# Alimentacion.net
KiCad netlist of a schematic drawn in Altium Designer
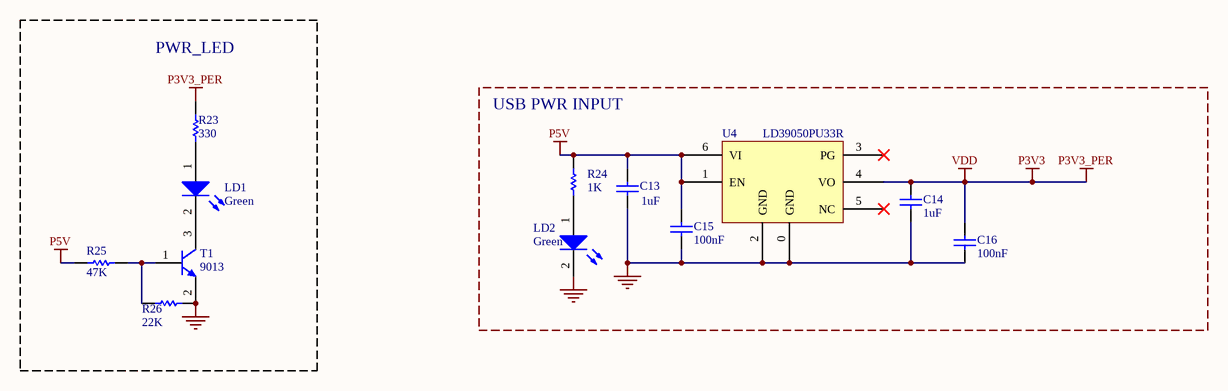
[diagram p0: Alimentacion.SchDoc]

(export (version "E")
  (design (tool "Eeschema 10.0.6"))
  (components
    (comp (ref "C13")
      (value "1uF")
      (footprint "0603C")
      (description "0603  X5R 1µF")
      (fields (field (name "TOLERANCE") "10%"))
      (libsource (lib "MB963_1") (part "CAP SMD 0603  X5R 1µF 25V 10%"))
    )
    (comp (ref "C14")
      (value "1uF")
      (footprint "0603C")
      (description "0603  X5R 1µF")
      (fields (field (name "TOLERANCE") "10%"))
      (libsource (lib "MB963_1") (part "CAP SMD 0603  X5R 1µF 25V 10%"))
    )
    (comp (ref "C15")
      (value "100nF")
      (footprint "0603C")
      (description "Capacitor 0402 / 0603 / 0805")
      (libsource (lib "MCD_TOOLS") (part "Capacitor_ST"))
    )
    (comp (ref "C16")
      (value "100nF")
      (footprint "0603C")
      (description "Capacitor 0402 / 0603 / 0805")
      (libsource (lib "MCD_TOOLS") (part "Capacitor_ST"))
    )
    (comp (ref "LD1")
      (value "Green")
      (footprint "0603D-G")
      (description "Typical RED, GREEN, YELLOW, AMBER GaAs LED")
      (fields (field (name "PUBLISHER") "Altium Limited"))
      (libsource (lib "") (part "LED2_1"))
    )
    (comp (ref "LD2")
      (value "Green")
      (footprint "0603D-G")
      (description "Typical RED, GREEN, YELLOW, AMBER GaAs LED")
      (fields (field (name "PUBLISHER") "Altium Limited"))
      (libsource (lib "Miscellaneous Devices") (part "LED2"))
    )
    (comp (ref "R23")
      (value "330")
      (footprint "0603R")
      (description "Resistor")
      (fields (field (name "PUBLISHER") "Altium Limited"))
      (libsource (lib "Miscellaneous Devices") (part "res1"))
    )
    (comp (ref "R24")
      (value "1K")
      (footprint "0603R")
      (description "Resistor 0402 / 0603 / 0805")
      (libsource (lib "MCD_TOOLS") (part "Resistor_ST"))
    )
    (comp (ref "R25")
      (value "47K")
      (footprint "0603R")
      (description "Resistor")
      (fields (field (name "PUBLISHER") "Altium Limited"))
      (libsource (lib "Miscellaneous Devices") (part "res1"))
    )
    (comp (ref "R26")
      (value "22K")
      (footprint "0603R")
      (description "Resistor")
      (fields (field (name "PUBLISHER") "Altium Limited"))
      (libsource (lib "Miscellaneous Devices") (part "res1"))
    )
    (comp (ref "T1")
      (value "9013")
      (footprint "SOT-23")
      (description "NPN Bipolar Transistor")
      (fields (field (name "PUBLISHER") "Altium Limited"))
      (libsource (lib "MB1167") (part "NPN"))
    )
    (comp (ref "U4")
      (value "LD39050PU33R")
      (footprint "DFN6_0R95_3x3_TP")
      (libsource (lib "MB1137") (part "LD39050P"))
    )
  )
  (nets
    (net (code "1") (name "GND") (class "Default")
      (node (ref "C13") (pin "2") (pinfunction "2_2") (pintype "passive"))
      (node (ref "C14") (pin "2") (pinfunction "2_2") (pintype "passive"))
      (node (ref "C15") (pin "1") (pinfunction "1_1") (pintype "passive"))
      (node (ref "C16") (pin "1") (pinfunction "1_1") (pintype "passive"))
      (node (ref "LD2") (pin "2") (pinfunction "K_2") (pintype "passive"))
      (node (ref "R26") (pin "1") (pinfunction "1_1") (pintype "passive"))
      (node (ref "T1") (pin "2") (pinfunction "E_2") (pintype "passive"))
      (node (ref "U4") (pin "0") (pinfunction "GND_0") (pintype "passive"))
      (node (ref "U4") (pin "2") (pinfunction "GND_2") (pintype "passive"))
    )
    (net (code "2") (name "Net-(LD1-A)") (class "Default")
      (node (ref "LD1") (pin "1") (pinfunction "A_1") (pintype "passive"))
      (node (ref "R23") (pin "1") (pinfunction "1_1") (pintype "passive"))
    )
    (net (code "3") (name "Net-(LD1-K)") (class "Default")
      (node (ref "LD1") (pin "2") (pinfunction "K_2") (pintype "passive"))
      (node (ref "T1") (pin "3") (pinfunction "C_3") (pintype "passive"))
    )
    (net (code "4") (name "Net-(LD2-A)") (class "Default")
      (node (ref "LD2") (pin "1") (pinfunction "A_1") (pintype "passive"))
      (node (ref "R24") (pin "1") (pinfunction "1_1") (pintype "passive"))
    )
    (net (code "5") (name "Net-(T1-B)") (class "Default")
      (node (ref "R25") (pin "2") (pinfunction "2_2") (pintype "passive"))
      (node (ref "R26") (pin "2") (pinfunction "2_2") (pintype "passive"))
      (node (ref "T1") (pin "1") (pinfunction "B_1") (pintype "passive"))
    )
    (net (code "6") (name "P3V3") (class "Default")
      (node (ref "C14") (pin "1") (pinfunction "1_1") (pintype "passive"))
      (node (ref "C16") (pin "2") (pinfunction "2_2") (pintype "passive"))
      (node (ref "R23") (pin "2") (pinfunction "2_2") (pintype "passive"))
      (node (ref "U4") (pin "4") (pinfunction "VO_4") (pintype "passive"))
    )
    (net (code "7") (name "P5V") (class "Default")
      (node (ref "C13") (pin "1") (pinfunction "1_1") (pintype "passive"))
      (node (ref "C15") (pin "2") (pinfunction "2_2") (pintype "passive"))
      (node (ref "R24") (pin "2") (pinfunction "2_2") (pintype "passive"))
      (node (ref "R25") (pin "1") (pinfunction "1_1") (pintype "passive"))
      (node (ref "U4") (pin "1") (pinfunction "EN_1") (pintype "passive"))
      (node (ref "U4") (pin "6") (pinfunction "VI_6") (pintype "passive"))
    )
    (net (code "8") (name "unconnected-(U4-NC-Pad5)") (class "Default")
      (node (ref "U4") (pin "5") (pinfunction "NC_5") (pintype "passive+no_connect"))
    )
    (net (code "9") (name "unconnected-(U4-PG-Pad3)") (class "Default")
      (node (ref "U4") (pin "3") (pinfunction "PG_3") (pintype "passive+no_connect"))
    )
  )
)
